# STM32_VDD_VSS.net
KiCad netlist of a schematic drawn in Altium Designer
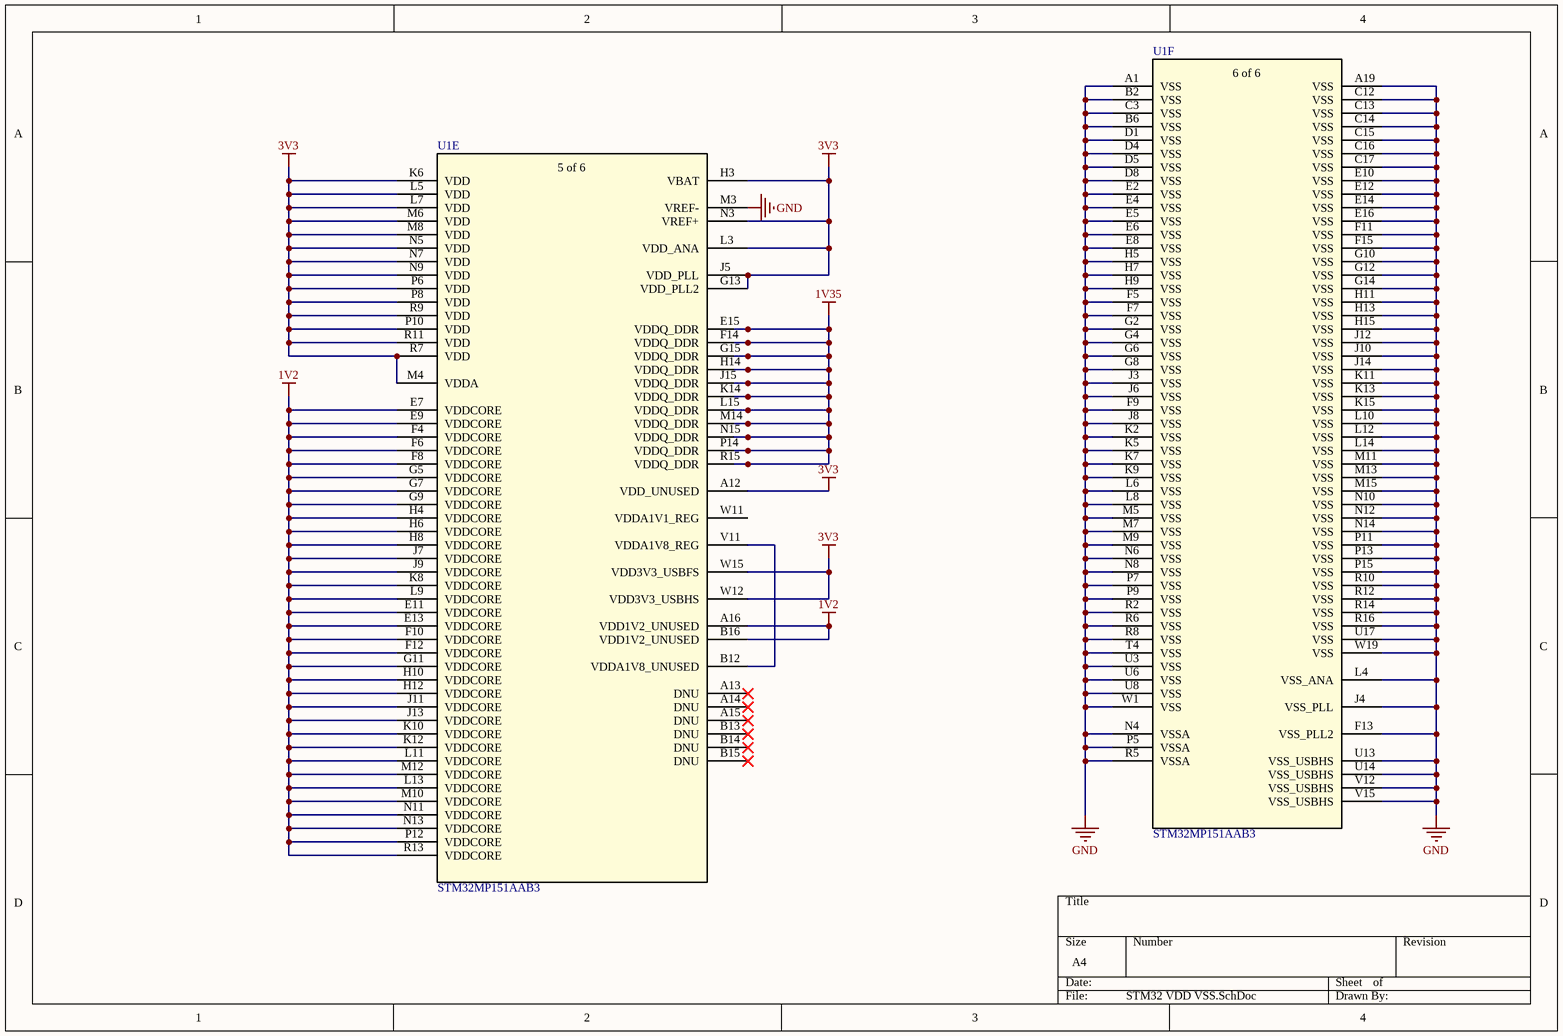
[diagram p0: STM32 VDD VSS.SchDoc]

(export (version "E")
  (design (tool "Eeschema 10.0.6"))
  (components
    (comp (ref "U1")
      (value "STM32MP151AAB3")
      (footprint "LFBGA354_16X16_STM")
      (description "No Description Available")
      (libsource (lib "Master") (part "STM32MP151AAB3"))
    )
  )
  (nets
    (net (code "1") (name "1V2") (class "Default")
      (node (ref "U1") (pin "A16") (pinfunction "VDD1V2_UNUSED_A16") (pintype "power_in"))
      (node (ref "U1") (pin "B16") (pinfunction "VDD1V2_UNUSED_B16") (pintype "power_in"))
      (node (ref "U1") (pin "E11") (pinfunction "VDDCORE_E11") (pintype "power_in"))
      (node (ref "U1") (pin "E13") (pinfunction "VDDCORE_E13") (pintype "power_in"))
      (node (ref "U1") (pin "E7") (pinfunction "VDDCORE_E7") (pintype "power_in"))
      (node (ref "U1") (pin "E9") (pinfunction "VDDCORE_E9") (pintype "power_in"))
      (node (ref "U1") (pin "F10") (pinfunction "VDDCORE_F10") (pintype "power_in"))
      (node (ref "U1") (pin "F12") (pinfunction "VDDCORE_F12") (pintype "power_in"))
      (node (ref "U1") (pin "F4") (pinfunction "VDDCORE_F4") (pintype "power_in"))
      (node (ref "U1") (pin "F6") (pinfunction "VDDCORE_F6") (pintype "power_in"))
      (node (ref "U1") (pin "F8") (pinfunction "VDDCORE_F8") (pintype "power_in"))
      (node (ref "U1") (pin "G11") (pinfunction "VDDCORE_G11") (pintype "power_in"))
      (node (ref "U1") (pin "G5") (pinfunction "VDDCORE_G5") (pintype "power_in"))
      (node (ref "U1") (pin "G7") (pinfunction "VDDCORE_G7") (pintype "power_in"))
      (node (ref "U1") (pin "G9") (pinfunction "VDDCORE_G9") (pintype "power_in"))
      (node (ref "U1") (pin "H10") (pinfunction "VDDCORE_H10") (pintype "power_in"))
      (node (ref "U1") (pin "H12") (pinfunction "VDDCORE_H12") (pintype "power_in"))
      (node (ref "U1") (pin "H4") (pinfunction "VDDCORE_H4") (pintype "power_in"))
      (node (ref "U1") (pin "H6") (pinfunction "VDDCORE_H6") (pintype "power_in"))
      (node (ref "U1") (pin "H8") (pinfunction "VDDCORE_H8") (pintype "power_in"))
      (node (ref "U1") (pin "J11") (pinfunction "VDDCORE_J11") (pintype "power_in"))
      (node (ref "U1") (pin "J13") (pinfunction "VDDCORE_J13") (pintype "power_in"))
      (node (ref "U1") (pin "J7") (pinfunction "VDDCORE_J7") (pintype "power_in"))
      (node (ref "U1") (pin "J9") (pinfunction "VDDCORE_J9") (pintype "power_in"))
      (node (ref "U1") (pin "K10") (pinfunction "VDDCORE_K10") (pintype "power_in"))
      (node (ref "U1") (pin "K12") (pinfunction "VDDCORE_K12") (pintype "power_in"))
      (node (ref "U1") (pin "K8") (pinfunction "VDDCORE_K8") (pintype "power_in"))
      (node (ref "U1") (pin "L11") (pinfunction "VDDCORE_L11") (pintype "power_in"))
      (node (ref "U1") (pin "L13") (pinfunction "VDDCORE_L13") (pintype "power_in"))
      (node (ref "U1") (pin "L9") (pinfunction "VDDCORE_L9") (pintype "power_in"))
      (node (ref "U1") (pin "M10") (pinfunction "VDDCORE_M10") (pintype "power_in"))
      (node (ref "U1") (pin "M12") (pinfunction "VDDCORE_M12") (pintype "power_in"))
      (node (ref "U1") (pin "N11") (pinfunction "VDDCORE_N11") (pintype "power_in"))
      (node (ref "U1") (pin "N13") (pinfunction "VDDCORE_N13") (pintype "power_in"))
      (node (ref "U1") (pin "P12") (pinfunction "VDDCORE_P12") (pintype "power_in"))
      (node (ref "U1") (pin "R13") (pinfunction "VDDCORE_R13") (pintype "power_in"))
    )
    (net (code "2") (name "1V35") (class "Default")
      (node (ref "U1") (pin "E15") (pinfunction "VDDQ_DDR_E15") (pintype "power_in"))
      (node (ref "U1") (pin "F14") (pinfunction "VDDQ_DDR_F14") (pintype "power_in"))
      (node (ref "U1") (pin "G15") (pinfunction "VDDQ_DDR_G15") (pintype "power_in"))
      (node (ref "U1") (pin "H14") (pinfunction "VDDQ_DDR_H14") (pintype "power_in"))
      (node (ref "U1") (pin "J15") (pinfunction "VDDQ_DDR_J15") (pintype "power_in"))
      (node (ref "U1") (pin "K14") (pinfunction "VDDQ_DDR_K14") (pintype "power_in"))
      (node (ref "U1") (pin "L15") (pinfunction "VDDQ_DDR_L15") (pintype "power_in"))
      (node (ref "U1") (pin "M14") (pinfunction "VDDQ_DDR_M14") (pintype "power_in"))
      (node (ref "U1") (pin "N15") (pinfunction "VDDQ_DDR_N15") (pintype "power_in"))
      (node (ref "U1") (pin "P14") (pinfunction "VDDQ_DDR_P14") (pintype "power_in"))
      (node (ref "U1") (pin "R15") (pinfunction "VDDQ_DDR_R15") (pintype "power_in"))
    )
    (net (code "3") (name "3V3") (class "Default")
      (node (ref "U1") (pin "A12") (pinfunction "VDD_UNUSED_A12") (pintype "power_in"))
      (node (ref "U1") (pin "G13") (pinfunction "VDD_PLL2_G13") (pintype "power_in"))
      (node (ref "U1") (pin "H3") (pinfunction "VBAT_H3") (pintype "power_in"))
      (node (ref "U1") (pin "J5") (pinfunction "VDD_PLL_J5") (pintype "power_in"))
      (node (ref "U1") (pin "K6") (pinfunction "VDD_K6") (pintype "power_in"))
      (node (ref "U1") (pin "L3") (pinfunction "VDD_ANA_L3") (pintype "power_in"))
      (node (ref "U1") (pin "L5") (pinfunction "VDD_L5") (pintype "power_in"))
      (node (ref "U1") (pin "L7") (pinfunction "VDD_L7") (pintype "power_in"))
      (node (ref "U1") (pin "M4") (pinfunction "VDDA_M4") (pintype "power_in"))
      (node (ref "U1") (pin "M6") (pinfunction "VDD_M6") (pintype "power_in"))
      (node (ref "U1") (pin "M8") (pinfunction "VDD_M8") (pintype "power_in"))
      (node (ref "U1") (pin "N3") (pinfunction "VREF+_N3") (pintype "power_in"))
      (node (ref "U1") (pin "N5") (pinfunction "VDD_N5") (pintype "power_in"))
      (node (ref "U1") (pin "N7") (pinfunction "VDD_N7") (pintype "power_in"))
      (node (ref "U1") (pin "N9") (pinfunction "VDD_N9") (pintype "power_in"))
      (node (ref "U1") (pin "P10") (pinfunction "VDD_P10") (pintype "power_in"))
      (node (ref "U1") (pin "P6") (pinfunction "VDD_P6") (pintype "power_in"))
      (node (ref "U1") (pin "P8") (pinfunction "VDD_P8") (pintype "power_in"))
      (node (ref "U1") (pin "R11") (pinfunction "VDD_R11") (pintype "power_in"))
      (node (ref "U1") (pin "R7") (pinfunction "VDD_R7") (pintype "power_in"))
      (node (ref "U1") (pin "R9") (pinfunction "VDD_R9") (pintype "power_in"))
      (node (ref "U1") (pin "W12") (pinfunction "VDD3V3_USBHS_W12") (pintype "power_in"))
      (node (ref "U1") (pin "W15") (pinfunction "VDD3V3_USBFS_W15") (pintype "power_in"))
    )
    (net (code "4") (name "GND") (class "Default")
      (node (ref "U1") (pin "A1") (pinfunction "VSS_A1") (pintype "power_in"))
      (node (ref "U1") (pin "A19") (pinfunction "VSS_A19") (pintype "power_in"))
      (node (ref "U1") (pin "B2") (pinfunction "VSS_B2") (pintype "power_in"))
      (node (ref "U1") (pin "B6") (pinfunction "VSS_B6") (pintype "power_in"))
      (node (ref "U1") (pin "C12") (pinfunction "VSS_C12") (pintype "power_in"))
      (node (ref "U1") (pin "C13") (pinfunction "VSS_C13") (pintype "power_in"))
      (node (ref "U1") (pin "C14") (pinfunction "VSS_C14") (pintype "power_in"))
      (node (ref "U1") (pin "C15") (pinfunction "VSS_C15") (pintype "power_in"))
      (node (ref "U1") (pin "C16") (pinfunction "VSS_C16") (pintype "power_in"))
      (node (ref "U1") (pin "C17") (pinfunction "VSS_C17") (pintype "power_in"))
      (node (ref "U1") (pin "C3") (pinfunction "VSS_C3") (pintype "power_in"))
      (node (ref "U1") (pin "D1") (pinfunction "VSS_D1") (pintype "power_in"))
      (node (ref "U1") (pin "D4") (pinfunction "VSS_D4") (pintype "power_in"))
      (node (ref "U1") (pin "D5") (pinfunction "VSS_D5") (pintype "power_in"))
      (node (ref "U1") (pin "D8") (pinfunction "VSS_D8") (pintype "power_in"))
      (node (ref "U1") (pin "E10") (pinfunction "VSS_E10") (pintype "power_in"))
      (node (ref "U1") (pin "E12") (pinfunction "VSS_E12") (pintype "power_in"))
      (node (ref "U1") (pin "E14") (pinfunction "VSS_E14") (pintype "power_in"))
      (node (ref "U1") (pin "E16") (pinfunction "VSS_E16") (pintype "power_in"))
      (node (ref "U1") (pin "E2") (pinfunction "VSS_E2") (pintype "power_in"))
      (node (ref "U1") (pin "E4") (pinfunction "VSS_E4") (pintype "power_in"))
      (node (ref "U1") (pin "E5") (pinfunction "VSS_E5") (pintype "power_in"))
      (node (ref "U1") (pin "E6") (pinfunction "VSS_E6") (pintype "power_in"))
      (node (ref "U1") (pin "E8") (pinfunction "VSS_E8") (pintype "power_in"))
      (node (ref "U1") (pin "F11") (pinfunction "VSS_F11") (pintype "power_in"))
      (node (ref "U1") (pin "F13") (pinfunction "VSS_PLL2_F13") (pintype "power_in"))
      (node (ref "U1") (pin "F15") (pinfunction "VSS_F15") (pintype "power_in"))
      (node (ref "U1") (pin "F5") (pinfunction "VSS_F5") (pintype "power_in"))
      (node (ref "U1") (pin "F7") (pinfunction "VSS_F7") (pintype "power_in"))
      (node (ref "U1") (pin "F9") (pinfunction "VSS_F9") (pintype "power_in"))
      (node (ref "U1") (pin "G10") (pinfunction "VSS_G10") (pintype "power_in"))
      (node (ref "U1") (pin "G12") (pinfunction "VSS_G12") (pintype "power_in"))
      (node (ref "U1") (pin "G14") (pinfunction "VSS_G14") (pintype "power_in"))
      (node (ref "U1") (pin "G2") (pinfunction "VSS_G2") (pintype "power_in"))
      (node (ref "U1") (pin "G4") (pinfunction "VSS_G4") (pintype "power_in"))
      (node (ref "U1") (pin "G6") (pinfunction "VSS_G6") (pintype "power_in"))
      (node (ref "U1") (pin "G8") (pinfunction "VSS_G8") (pintype "power_in"))
      (node (ref "U1") (pin "H11") (pinfunction "VSS_H11") (pintype "power_in"))
      (node (ref "U1") (pin "H13") (pinfunction "VSS_H13") (pintype "power_in"))
      (node (ref "U1") (pin "H15") (pinfunction "VSS_H15") (pintype "power_in"))
      (node (ref "U1") (pin "H5") (pinfunction "VSS_H5") (pintype "power_in"))
      (node (ref "U1") (pin "H7") (pinfunction "VSS_H7") (pintype "power_in"))
      (node (ref "U1") (pin "H9") (pinfunction "VSS_H9") (pintype "power_in"))
      (node (ref "U1") (pin "J10") (pinfunction "VSS_J10") (pintype "power_in"))
      (node (ref "U1") (pin "J12") (pinfunction "VSS_J12") (pintype "power_in"))
      (node (ref "U1") (pin "J14") (pinfunction "VSS_J14") (pintype "power_in"))
      (node (ref "U1") (pin "J3") (pinfunction "VSS_J3") (pintype "power_in"))
      (node (ref "U1") (pin "J4") (pinfunction "VSS_PLL_J4") (pintype "power_in"))
      (node (ref "U1") (pin "J6") (pinfunction "VSS_J6") (pintype "power_in"))
      (node (ref "U1") (pin "J8") (pinfunction "VSS_J8") (pintype "power_in"))
      (node (ref "U1") (pin "K11") (pinfunction "VSS_K11") (pintype "power_in"))
      (node (ref "U1") (pin "K13") (pinfunction "VSS_K13") (pintype "power_in"))
      (node (ref "U1") (pin "K15") (pinfunction "VSS_K15") (pintype "power_in"))
      (node (ref "U1") (pin "K2") (pinfunction "VSS_K2") (pintype "power_in"))
      (node (ref "U1") (pin "K5") (pinfunction "VSS_K5") (pintype "power_in"))
      (node (ref "U1") (pin "K7") (pinfunction "VSS_K7") (pintype "power_in"))
      (node (ref "U1") (pin "K9") (pinfunction "VSS_K9") (pintype "power_in"))
      (node (ref "U1") (pin "L10") (pinfunction "VSS_L10") (pintype "power_in"))
      (node (ref "U1") (pin "L12") (pinfunction "VSS_L12") (pintype "power_in"))
      (node (ref "U1") (pin "L14") (pinfunction "VSS_L14") (pintype "power_in"))
      (node (ref "U1") (pin "L4") (pinfunction "VSS_ANA_L4") (pintype "power_in"))
      (node (ref "U1") (pin "L6") (pinfunction "VSS_L6") (pintype "power_in"))
      (node (ref "U1") (pin "L8") (pinfunction "VSS_L8") (pintype "power_in"))
      (node (ref "U1") (pin "M11") (pinfunction "VSS_M11") (pintype "power_in"))
      (node (ref "U1") (pin "M13") (pinfunction "VSS_M13") (pintype "power_in"))
      (node (ref "U1") (pin "M15") (pinfunction "VSS_M15") (pintype "power_in"))
      (node (ref "U1") (pin "M3") (pinfunction "VREF-_M3") (pintype "power_in"))
      (node (ref "U1") (pin "M5") (pinfunction "VSS_M5") (pintype "power_in"))
      (node (ref "U1") (pin "M7") (pinfunction "VSS_M7") (pintype "power_in"))
      (node (ref "U1") (pin "M9") (pinfunction "VSS_M9") (pintype "power_in"))
      (node (ref "U1") (pin "N10") (pinfunction "VSS_N10") (pintype "power_in"))
      (node (ref "U1") (pin "N12") (pinfunction "VSS_N12") (pintype "power_in"))
      (node (ref "U1") (pin "N14") (pinfunction "VSS_N14") (pintype "power_in"))
      (node (ref "U1") (pin "N4") (pinfunction "VSSA_N4") (pintype "power_in"))
      (node (ref "U1") (pin "N6") (pinfunction "VSS_N6") (pintype "power_in"))
      (node (ref "U1") (pin "N8") (pinfunction "VSS_N8") (pintype "power_in"))
      (node (ref "U1") (pin "P11") (pinfunction "VSS_P11") (pintype "power_in"))
      (node (ref "U1") (pin "P13") (pinfunction "VSS_P13") (pintype "power_in"))
      (node (ref "U1") (pin "P15") (pinfunction "VSS_P15") (pintype "power_in"))
      (node (ref "U1") (pin "P5") (pinfunction "VSSA_P5") (pintype "power_in"))
      (node (ref "U1") (pin "P7") (pinfunction "VSS_P7") (pintype "power_in"))
      (node (ref "U1") (pin "P9") (pinfunction "VSS_P9") (pintype "power_in"))
      (node (ref "U1") (pin "R10") (pinfunction "VSS_R10") (pintype "power_in"))
      (node (ref "U1") (pin "R12") (pinfunction "VSS_R12") (pintype "power_in"))
      (node (ref "U1") (pin "R14") (pinfunction "VSS_R14") (pintype "power_in"))
      (node (ref "U1") (pin "R16") (pinfunction "VSS_R16") (pintype "power_in"))
      (node (ref "U1") (pin "R2") (pinfunction "VSS_R2") (pintype "power_in"))
      (node (ref "U1") (pin "R5") (pinfunction "VSSA_R5") (pintype "power_in"))
      (node (ref "U1") (pin "R6") (pinfunction "VSS_R6") (pintype "power_in"))
      (node (ref "U1") (pin "R8") (pinfunction "VSS_R8") (pintype "power_in"))
      (node (ref "U1") (pin "T4") (pinfunction "VSS_T4") (pintype "power_in"))
      (node (ref "U1") (pin "U13") (pinfunction "VSS_USBHS_U13") (pintype "power_in"))
      (node (ref "U1") (pin "U14") (pinfunction "VSS_USBHS_U14") (pintype "power_in"))
      (node (ref "U1") (pin "U17") (pinfunction "VSS_U17") (pintype "power_in"))
      (node (ref "U1") (pin "U3") (pinfunction "VSS_U3") (pintype "power_in"))
      (node (ref "U1") (pin "U6") (pinfunction "VSS_U6") (pintype "power_in"))
      (node (ref "U1") (pin "U8") (pinfunction "VSS_U8") (pintype "power_in"))
      (node (ref "U1") (pin "V12") (pinfunction "VSS_USBHS_V12") (pintype "power_in"))
      (node (ref "U1") (pin "V15") (pinfunction "VSS_USBHS_V15") (pintype "power_in"))
      (node (ref "U1") (pin "W1") (pinfunction "VSS_W1") (pintype "power_in"))
      (node (ref "U1") (pin "W19") (pinfunction "VSS_W19") (pintype "power_in"))
    )
    (net (code "5") (name "Net-(U1E-VDDA1V8_REG)") (class "Default")
      (node (ref "U1") (pin "B12") (pinfunction "VDDA1V8_UNUSED_B12") (pintype "power_in"))
      (node (ref "U1") (pin "V11") (pinfunction "VDDA1V8_REG_V11") (pintype "power_in"))
    )
    (net (code "6") (name "unconnected-(U1E-DNU-PadA13)") (class "Default")
      (node (ref "U1") (pin "A13") (pinfunction "DNU_A13") (pintype "passive+no_connect"))
    )
    (net (code "7") (name "unconnected-(U1E-DNU-PadA14)") (class "Default")
      (node (ref "U1") (pin "A14") (pinfunction "DNU_A14") (pintype "passive+no_connect"))
    )
    (net (code "8") (name "unconnected-(U1E-DNU-PadA15)") (class "Default")
      (node (ref "U1") (pin "A15") (pinfunction "DNU_A15") (pintype "passive+no_connect"))
    )
    (net (code "9") (name "unconnected-(U1E-DNU-PadB13)") (class "Default")
      (node (ref "U1") (pin "B13") (pinfunction "DNU_B13") (pintype "passive+no_connect"))
    )
    (net (code "10") (name "unconnected-(U1E-DNU-PadB14)") (class "Default")
      (node (ref "U1") (pin "B14") (pinfunction "DNU_B14") (pintype "passive+no_connect"))
    )
    (net (code "11") (name "unconnected-(U1E-DNU-PadB15)") (class "Default")
      (node (ref "U1") (pin "B15") (pinfunction "DNU_B15") (pintype "passive+no_connect"))
    )
    (net (code "12") (name "unconnected-(U1E-VDDA1V1_REG-PadW11)") (class "Default")
      (node (ref "U1") (pin "W11") (pinfunction "VDDA1V1_REG_W11") (pintype "power_in"))
    )
  )
)
